# Piezo-Pulse-Sensor.net
KiCad netlist of a schematic drawn in EAGLE
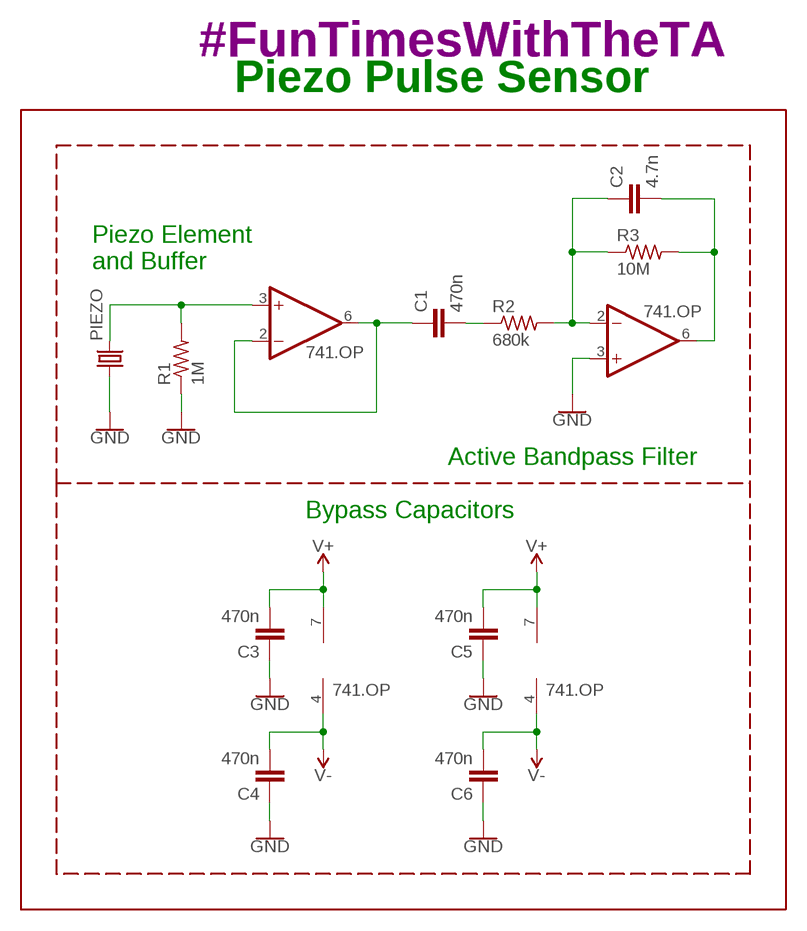
[diagram p0: schematic, sheet 1]

(export (version "E")
  (design (tool "Eeschema 10.0.6"))
  (components
    (comp (ref "C1")
      (value "470n")
      (footprint "eagle-import:C0402")
      (libsource (lib "eagle-import") (part "CAPACITOR0402"))
    )
    (comp (ref "C2")
      (value "4.7n")
      (footprint "eagle-import:C0402")
      (libsource (lib "eagle-import") (part "CAPACITOR0402"))
    )
    (comp (ref "C3")
      (value "470n")
      (footprint "eagle-import:C0402")
      (libsource (lib "eagle-import") (part "CAPACITOR0402"))
    )
    (comp (ref "C4")
      (value "470n")
      (footprint "eagle-import:C0402")
      (libsource (lib "eagle-import") (part "CAPACITOR0402"))
    )
    (comp (ref "C5")
      (value "470n")
      (footprint "eagle-import:C0402")
      (libsource (lib "eagle-import") (part "CAPACITOR0402"))
    )
    (comp (ref "C6")
      (value "470n")
      (footprint "eagle-import:C0402")
      (libsource (lib "eagle-import") (part "CAPACITOR0402"))
    )
    (comp (ref "OP1")
      (value "741.OP")
      (footprint "eagle-import:DIL08")
      (libsource (lib "eagle-import") (part "741.OP"))
    )
    (comp (ref "OP2")
      (value "741.OP")
      (footprint "eagle-import:DIL08")
      (libsource (lib "eagle-import") (part "741.OP"))
    )
    (comp (ref "PIEZO")
      (value "PIEZO-LEADED")
      (footprint "eagle-import:VIA")
      (libsource (lib "eagle-import") (part "PIEZO-LEADED"))
    )
    (comp (ref "R1")
      (value "1M")
      (footprint "eagle-import:R0402")
      (libsource (lib "eagle-import") (part "RESISTOR0402"))
    )
    (comp (ref "R2")
      (value "680k")
      (footprint "eagle-import:R0402")
      (libsource (lib "eagle-import") (part "RESISTOR0402"))
    )
    (comp (ref "R3")
      (value "10M")
      (footprint "eagle-import:R0402")
      (libsource (lib "eagle-import") (part "RESISTOR0402"))
    )
  )
  (nets
    (net (code "1") (name "GND") (class "Default")
      (node (ref "C3") (pin "1") (pinfunction "1_1") (pintype "passive"))
      (node (ref "C4") (pin "1") (pinfunction "1_1") (pintype "passive"))
      (node (ref "C5") (pin "1") (pinfunction "1_1") (pintype "passive"))
      (node (ref "C6") (pin "1") (pinfunction "1_1") (pintype "passive"))
      (node (ref "OP2") (pin "3") (pinfunction "+IN_3") (pintype "input"))
      (node (ref "PIEZO") (pin "1") (pinfunction "1_1") (pintype "passive"))
      (node (ref "R1") (pin "1") (pinfunction "1_1") (pintype "passive"))
    )
    (net (code "2") (name "Net-(C1-Pad2)") (class "Default")
      (node (ref "C1") (pin "2") (pinfunction "2_2") (pintype "passive"))
      (node (ref "R2") (pin "1") (pinfunction "1_1") (pintype "passive"))
    )
    (net (code "3") (name "Net-(OP1A-+IN)") (class "Default")
      (node (ref "OP1") (pin "3") (pinfunction "+IN_3") (pintype "input"))
      (node (ref "PIEZO") (pin "2") (pinfunction "2_2") (pintype "passive"))
      (node (ref "R1") (pin "2") (pinfunction "2_2") (pintype "passive"))
    )
    (net (code "4") (name "Net-(OP1A--IN)") (class "Default")
      (node (ref "C1") (pin "1") (pinfunction "1_1") (pintype "passive"))
      (node (ref "OP1") (pin "2") (pinfunction "-IN_2") (pintype "input"))
      (node (ref "OP1") (pin "6") (pinfunction "OUT_6") (pintype "output"))
    )
    (net (code "5") (name "Net-(OP2A--IN)") (class "Default")
      (node (ref "C2") (pin "1") (pinfunction "1_1") (pintype "passive"))
      (node (ref "OP2") (pin "2") (pinfunction "-IN_2") (pintype "input"))
      (node (ref "R2") (pin "2") (pinfunction "2_2") (pintype "passive"))
      (node (ref "R3") (pin "1") (pinfunction "1_1") (pintype "passive"))
    )
    (net (code "6") (name "Net-(OP2A-OUT)") (class "Default")
      (node (ref "C2") (pin "2") (pinfunction "2_2") (pintype "passive"))
      (node (ref "OP2") (pin "6") (pinfunction "OUT_6") (pintype "output"))
      (node (ref "R3") (pin "2") (pinfunction "2_2") (pintype "passive"))
    )
    (net (code "7") (name "V+") (class "Default")
      (node (ref "C3") (pin "2") (pinfunction "2_2") (pintype "passive"))
      (node (ref "C5") (pin "2") (pinfunction "2_2") (pintype "passive"))
      (node (ref "OP1") (pin "7") (pinfunction "V+_7") (pintype "power_in"))
      (node (ref "OP2") (pin "7") (pinfunction "V+_7") (pintype "power_in"))
    )
    (net (code "8") (name "V-") (class "Default")
      (node (ref "C4") (pin "2") (pinfunction "2_2") (pintype "passive"))
      (node (ref "C6") (pin "2") (pinfunction "2_2") (pintype "passive"))
      (node (ref "OP1") (pin "4") (pinfunction "V-_4") (pintype "power_in"))
      (node (ref "OP2") (pin "4") (pinfunction "V-_4") (pintype "power_in"))
    )
  )
)
